# v1_0.net
KiCad netlist of a schematic drawn in Altium Designer
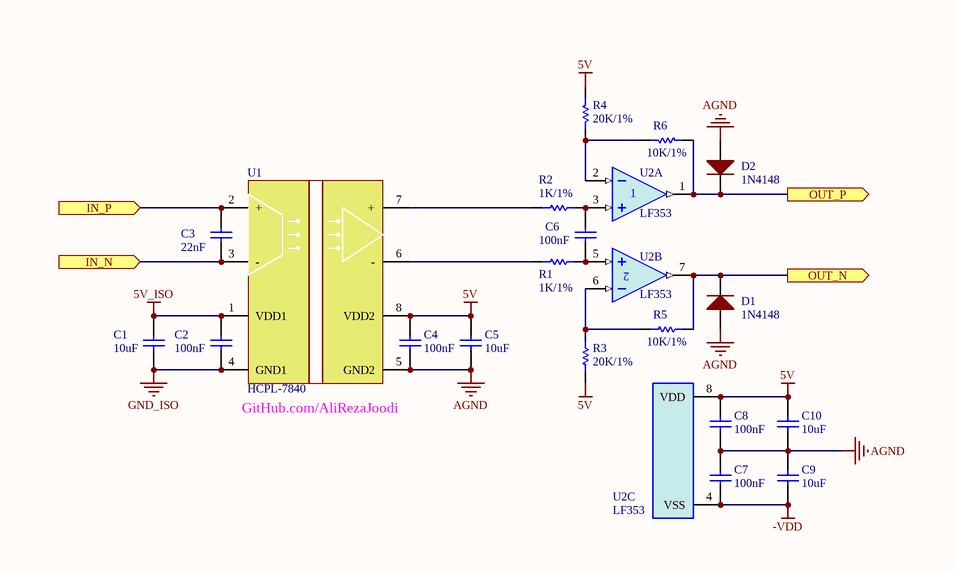
[diagram p0: v1.0.SchDoc]

(export (version "E")
  (design (tool "Eeschema 10.0.6"))
  (components
    (comp (ref "C1")
      (value "10uF")
      (footprint "Capacitor_Ceramic:SMD_0805")
      (description "Capacitor, Ceramic Multilayer, 25V, 10%")
      (libsource (lib "General") (part "Capacitor_Ceramic"))
    )
    (comp (ref "C2")
      (value "100nF")
      (footprint "Capacitor_Ceramic:SMD_0805")
      (description "Capacitor, Ceramic Multilayer, 25V, 10%")
      (libsource (lib "General") (part "Capacitor_Ceramic"))
    )
    (comp (ref "C3")
      (value "22nF")
      (footprint "Capacitor_Ceramic:SMD_0805")
      (description "Capacitor, Ceramic Multilayer, 25V, 10%")
      (libsource (lib "General") (part "Capacitor_Ceramic"))
    )
    (comp (ref "C4")
      (value "100nF")
      (footprint "Capacitor_Ceramic:SMD_0805")
      (description "Capacitor, Ceramic Multilayer, 25V, 10%")
      (libsource (lib "General") (part "Capacitor_Ceramic"))
    )
    (comp (ref "C5")
      (value "10uF")
      (footprint "Capacitor_Ceramic:SMD_0805")
      (description "Capacitor, Ceramic Multilayer, 25V, 10%")
      (libsource (lib "General") (part "Capacitor_Ceramic"))
    )
    (comp (ref "C6")
      (value "100nF")
      (footprint "Capacitor_Ceramic:SMD_0805")
      (description "Capacitor, Ceramic Multilayer, 25V, 10%")
      (libsource (lib "General") (part "Capacitor_Ceramic"))
    )
    (comp (ref "C7")
      (value "100nF")
      (footprint "Capacitor_Ceramic:SMD_0805")
      (description "Capacitor, Ceramic Multilayer, 25V, 10%")
      (libsource (lib "General") (part "Capacitor_Ceramic"))
    )
    (comp (ref "C8")
      (value "100nF")
      (footprint "Capacitor_Ceramic:SMD_0805")
      (description "Capacitor, Ceramic Multilayer, 25V, 10%")
      (libsource (lib "General") (part "Capacitor_Ceramic"))
    )
    (comp (ref "C9")
      (value "10uF")
      (footprint "Capacitor_Ceramic:SMD_0805")
      (description "Capacitor, Ceramic Multilayer, 25V, 10%")
      (libsource (lib "General") (part "Capacitor_Ceramic"))
    )
    (comp (ref "C10")
      (value "10uF")
      (footprint "Capacitor_Ceramic:SMD_0805")
      (description "Capacitor, Ceramic Multilayer, 25V, 10%")
      (libsource (lib "General") (part "Capacitor_Ceramic"))
    )
    (comp (ref "D1")
      (value "1N4148")
      (footprint "SMD_DO-213AA")
      (description "Diode")
      (fields (field (name "MANUFACTURER") "Microchip Technology") (field (name "PART NUMBER") "1N4148UR-1"))
      (libsource (lib "General") (part "Diode_2Form"))
    )
    (comp (ref "D2")
      (value "1N4148")
      (footprint "SMD_DO-213AA")
      (description "Diode")
      (fields (field (name "MANUFACTURER") "Microchip Technology") (field (name "PART NUMBER") "1N4148UR-1"))
      (libsource (lib "General") (part "Diode_2Form"))
    )
    (comp (ref "R1")
      (value "1K/1%")
      (footprint "SMD_0805")
      (description "Resistor, 1/8W, 1%")
      (libsource (lib "General") (part "Resistor"))
    )
    (comp (ref "R2")
      (value "1K/1%")
      (footprint "SMD_0805")
      (description "Resistor, 1/8W, 1%")
      (libsource (lib "General") (part "Resistor"))
    )
    (comp (ref "R3")
      (value "20K/1%")
      (footprint "SMD_0805")
      (description "Resistor, 1/8W, 1%")
      (libsource (lib "General") (part "Resistor"))
    )
    (comp (ref "R4")
      (value "20K/1%")
      (footprint "SMD_0805")
      (description "Resistor, 1/8W, 1%")
      (libsource (lib "") (part "Resistor_1"))
    )
    (comp (ref "R5")
      (value "10K/1%")
      (footprint "SMD_0805")
      (description "Resistor, 1/8W, 1%")
      (libsource (lib "General") (part "Resistor"))
    )
    (comp (ref "R6")
      (value "10K/1%")
      (footprint "SMD_0805")
      (description "Resistor, 1/8W, 1%")
      (libsource (lib "General") (part "Resistor"))
    )
    (comp (ref "U1")
      (value "HCPL-7840")
      (footprint "DIP_8")
      (description "Isolation Amplifier")
      (libsource (lib "IC") (part "HCPL-7840"))
    )
    (comp (ref "U2")
      (value "LF353")
      (footprint "SOIC127P600-8CM")
      (description "IC, Op-Amp")
      (fields (field (name "MANUFACTURER") "Texas Instruments") (field (name "PART NUMBER") "LF353P"))
      (libsource (lib "") (part "Op-Amp_Form1_1"))
    )
  )
  (nets
    (net (code "1") (name "-VDD") (class "Default")
      (node (ref "C7") (pin "1") (pinfunction "1_1") (pintype "passive"))
      (node (ref "C9") (pin "2") (pinfunction "2_2") (pintype "passive"))
      (node (ref "U2") (pin "4") (pinfunction "VSS_4") (pintype "power_in"))
    )
    (net (code "2") (name "/IN_N") (class "Default")
      (node (ref "C3") (pin "2") (pinfunction "2_2") (pintype "passive"))
      (node (ref "U1") (pin "3") (pinfunction "-_3") (pintype "passive"))
    )
    (net (code "3") (name "/IN_P") (class "Default")
      (node (ref "C3") (pin "1") (pinfunction "1_1") (pintype "passive"))
      (node (ref "U1") (pin "2") (pinfunction "+_2") (pintype "passive"))
    )
    (net (code "4") (name "/OUT_N") (class "Default")
      (node (ref "D1") (pin "2") (pinfunction "K_2") (pintype "passive"))
      (node (ref "R5") (pin "1") (pinfunction "1_1") (pintype "passive"))
      (node (ref "U2") (pin "7") (pinfunction "OUT_7") (pintype "output"))
    )
    (net (code "5") (name "/OUT_P") (class "Default")
      (node (ref "D2") (pin "2") (pinfunction "K_2") (pintype "passive"))
      (node (ref "R6") (pin "1") (pinfunction "1_1") (pintype "passive"))
      (node (ref "U2") (pin "1") (pinfunction "OUT_1") (pintype "output"))
    )
    (net (code "6") (name "5V") (class "Default")
      (node (ref "C10") (pin "1") (pinfunction "1_1") (pintype "passive"))
      (node (ref "C4") (pin "2") (pinfunction "2_2") (pintype "passive"))
      (node (ref "C5") (pin "1") (pinfunction "1_1") (pintype "passive"))
      (node (ref "C8") (pin "2") (pinfunction "2_2") (pintype "passive"))
      (node (ref "R3") (pin "2") (pinfunction "2_2") (pintype "passive"))
      (node (ref "R4") (pin "2") (pinfunction "2_2") (pintype "passive"))
      (node (ref "U1") (pin "8") (pinfunction "VDD2_8") (pintype "passive"))
      (node (ref "U2") (pin "8") (pinfunction "VDD_8") (pintype "passive"))
    )
    (net (code "7") (name "5V_ISO") (class "Default")
      (node (ref "C1") (pin "1") (pinfunction "1_1") (pintype "passive"))
      (node (ref "C2") (pin "2") (pinfunction "2_2") (pintype "passive"))
      (node (ref "U1") (pin "1") (pinfunction "VDD1_1") (pintype "passive"))
    )
    (net (code "8") (name "AGND") (class "Default")
      (node (ref "C10") (pin "2") (pinfunction "2_2") (pintype "passive"))
      (node (ref "C4") (pin "1") (pinfunction "1_1") (pintype "passive"))
      (node (ref "C5") (pin "2") (pinfunction "2_2") (pintype "passive"))
      (node (ref "C7") (pin "2") (pinfunction "2_2") (pintype "passive"))
      (node (ref "C8") (pin "1") (pinfunction "1_1") (pintype "passive"))
      (node (ref "C9") (pin "1") (pinfunction "1_1") (pintype "passive"))
      (node (ref "D1") (pin "1") (pinfunction "A_1") (pintype "passive"))
      (node (ref "D2") (pin "1") (pinfunction "A_1") (pintype "passive"))
      (node (ref "U1") (pin "5") (pinfunction "GND2_5") (pintype "passive"))
    )
    (net (code "9") (name "GND_ISO") (class "Default")
      (node (ref "C1") (pin "2") (pinfunction "2_2") (pintype "passive"))
      (node (ref "C2") (pin "1") (pinfunction "1_1") (pintype "passive"))
      (node (ref "U1") (pin "4") (pinfunction "GND1_4") (pintype "passive"))
    )
    (net (code "10") (name "Net-(R1-Pad2)") (class "Default")
      (node (ref "R1") (pin "2") (pinfunction "2_2") (pintype "passive"))
      (node (ref "U1") (pin "6") (pinfunction "-_6") (pintype "passive"))
    )
    (net (code "11") (name "Net-(R2-Pad2)") (class "Default")
      (node (ref "R2") (pin "2") (pinfunction "2_2") (pintype "passive"))
      (node (ref "U1") (pin "7") (pinfunction "+_7") (pintype "passive"))
    )
    (net (code "12") (name "Net-(U2A-IN+)") (class "Default")
      (node (ref "C6") (pin "2") (pinfunction "2_2") (pintype "passive"))
      (node (ref "R2") (pin "1") (pinfunction "1_1") (pintype "passive"))
      (node (ref "U2") (pin "3") (pinfunction "IN+_3") (pintype "input"))
    )
    (net (code "13") (name "Net-(U2A-IN-)") (class "Default")
      (node (ref "R4") (pin "1") (pinfunction "1_1") (pintype "passive"))
      (node (ref "R6") (pin "2") (pinfunction "2_2") (pintype "passive"))
      (node (ref "U2") (pin "2") (pinfunction "IN-_2") (pintype "input"))
    )
    (net (code "14") (name "Net-(U2B-IN+)") (class "Default")
      (node (ref "C6") (pin "1") (pinfunction "1_1") (pintype "passive"))
      (node (ref "R1") (pin "1") (pinfunction "1_1") (pintype "passive"))
      (node (ref "U2") (pin "5") (pinfunction "IN+_5") (pintype "input"))
    )
    (net (code "15") (name "Net-(U2B-IN-)") (class "Default")
      (node (ref "R3") (pin "1") (pinfunction "1_1") (pintype "passive"))
      (node (ref "R5") (pin "2") (pinfunction "2_2") (pintype "passive"))
      (node (ref "U2") (pin "6") (pinfunction "IN-_6") (pintype "input"))
    )
  )
)
